# GUI_Switches.net
KiCad netlist of a schematic drawn in EAGLE
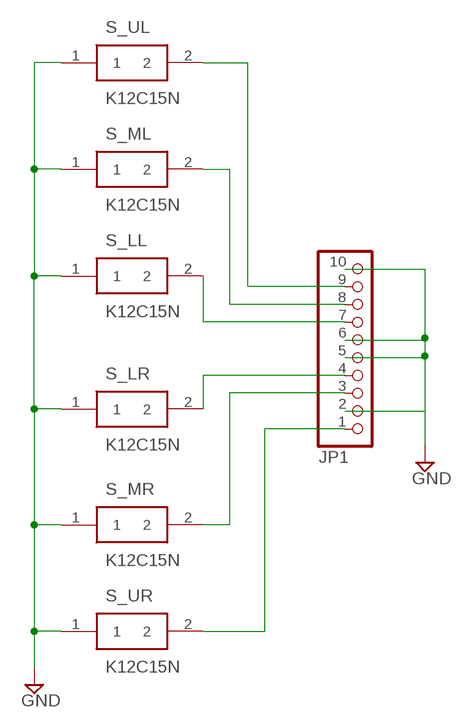
[diagram p0: schematic, sheet 1]

(export (version "E")
  (design (tool "Eeschema 10.0.6"))
  (components
    (comp (ref "JP1")
      (value "PINHD-1X10/90")
      (footprint "eagle-import:1X10_90")
      (libsource (lib "eagle-import") (part "PINHD-1X10/90"))
    )
    (comp (ref "S_LL")
      (value "K12C15N")
      (footprint "eagle-import:K12C15N")
      (fields (field (name "MOUSER_PART_NUMBER") "611-K12C15N") (field (name "RS_PART_NUMBER") "7874858"))
      (libsource (lib "eagle-import") (part "K12C15N"))
    )
    (comp (ref "S_LR")
      (value "K12C15N")
      (footprint "eagle-import:K12C15N")
      (fields (field (name "MOUSER_PART_NUMBER") "611-K12C15N") (field (name "RS_PART_NUMBER") "7874858"))
      (libsource (lib "eagle-import") (part "K12C15N"))
    )
    (comp (ref "S_ML")
      (value "K12C15N")
      (footprint "eagle-import:K12C15N")
      (fields (field (name "MOUSER_PART_NUMBER") "611-K12C15N") (field (name "RS_PART_NUMBER") "7874858"))
      (libsource (lib "eagle-import") (part "K12C15N"))
    )
    (comp (ref "S_MR")
      (value "K12C15N")
      (footprint "eagle-import:K12C15N")
      (fields (field (name "MOUSER_PART_NUMBER") "611-K12C15N") (field (name "RS_PART_NUMBER") "7874858"))
      (libsource (lib "eagle-import") (part "K12C15N"))
    )
    (comp (ref "S_UL")
      (value "K12C15N")
      (footprint "eagle-import:K12C15N")
      (fields (field (name "MOUSER_PART_NUMBER") "611-K12C15N") (field (name "RS_PART_NUMBER") "7874858"))
      (libsource (lib "eagle-import") (part "K12C15N"))
    )
    (comp (ref "S_UR")
      (value "K12C15N")
      (footprint "eagle-import:K12C15N")
      (fields (field (name "MOUSER_PART_NUMBER") "611-K12C15N") (field (name "RS_PART_NUMBER") "7874858"))
      (libsource (lib "eagle-import") (part "K12C15N"))
    )
  )
  (nets
    (net (code "1") (name "GND") (class "Default")
      (node (ref "JP1") (pin "10") (pinfunction "10_10") (pintype "passive"))
      (node (ref "JP1") (pin "2") (pinfunction "2_2") (pintype "passive"))
      (node (ref "JP1") (pin "5") (pinfunction "5_5") (pintype "passive"))
      (node (ref "JP1") (pin "6") (pinfunction "6_6") (pintype "passive"))
      (node (ref "S_LL") (pin "1") (pinfunction "1_1") (pintype "bidirectional"))
      (node (ref "S_LR") (pin "1") (pinfunction "1_1") (pintype "bidirectional"))
      (node (ref "S_ML") (pin "1") (pinfunction "1_1") (pintype "bidirectional"))
      (node (ref "S_MR") (pin "1") (pinfunction "1_1") (pintype "bidirectional"))
      (node (ref "S_UL") (pin "1") (pinfunction "1_1") (pintype "bidirectional"))
      (node (ref "S_UR") (pin "1") (pinfunction "1_1") (pintype "bidirectional"))
    )
    (net (code "2") (name "Net-(JP1-Pad1)") (class "Default")
      (node (ref "JP1") (pin "1") (pinfunction "1_1") (pintype "passive"))
      (node (ref "S_UR") (pin "2") (pinfunction "2_2") (pintype "bidirectional"))
    )
    (net (code "3") (name "Net-(JP1-Pad3)") (class "Default")
      (node (ref "JP1") (pin "3") (pinfunction "3_3") (pintype "passive"))
      (node (ref "S_MR") (pin "2") (pinfunction "2_2") (pintype "bidirectional"))
    )
    (net (code "4") (name "Net-(JP1-Pad4)") (class "Default")
      (node (ref "JP1") (pin "4") (pinfunction "4_4") (pintype "passive"))
      (node (ref "S_LR") (pin "2") (pinfunction "2_2") (pintype "bidirectional"))
    )
    (net (code "5") (name "Net-(JP1-Pad7)") (class "Default")
      (node (ref "JP1") (pin "7") (pinfunction "7_7") (pintype "passive"))
      (node (ref "S_LL") (pin "2") (pinfunction "2_2") (pintype "bidirectional"))
    )
    (net (code "6") (name "Net-(JP1-Pad8)") (class "Default")
      (node (ref "JP1") (pin "8") (pinfunction "8_8") (pintype "passive"))
      (node (ref "S_ML") (pin "2") (pinfunction "2_2") (pintype "bidirectional"))
    )
    (net (code "7") (name "Net-(JP1-Pad9)") (class "Default")
      (node (ref "JP1") (pin "9") (pinfunction "9_9") (pintype "passive"))
      (node (ref "S_UL") (pin "2") (pinfunction "2_2") (pintype "bidirectional"))
    )
  )
)
